# WIFI_BT.net
KiCad netlist of a schematic drawn in Altium Designer
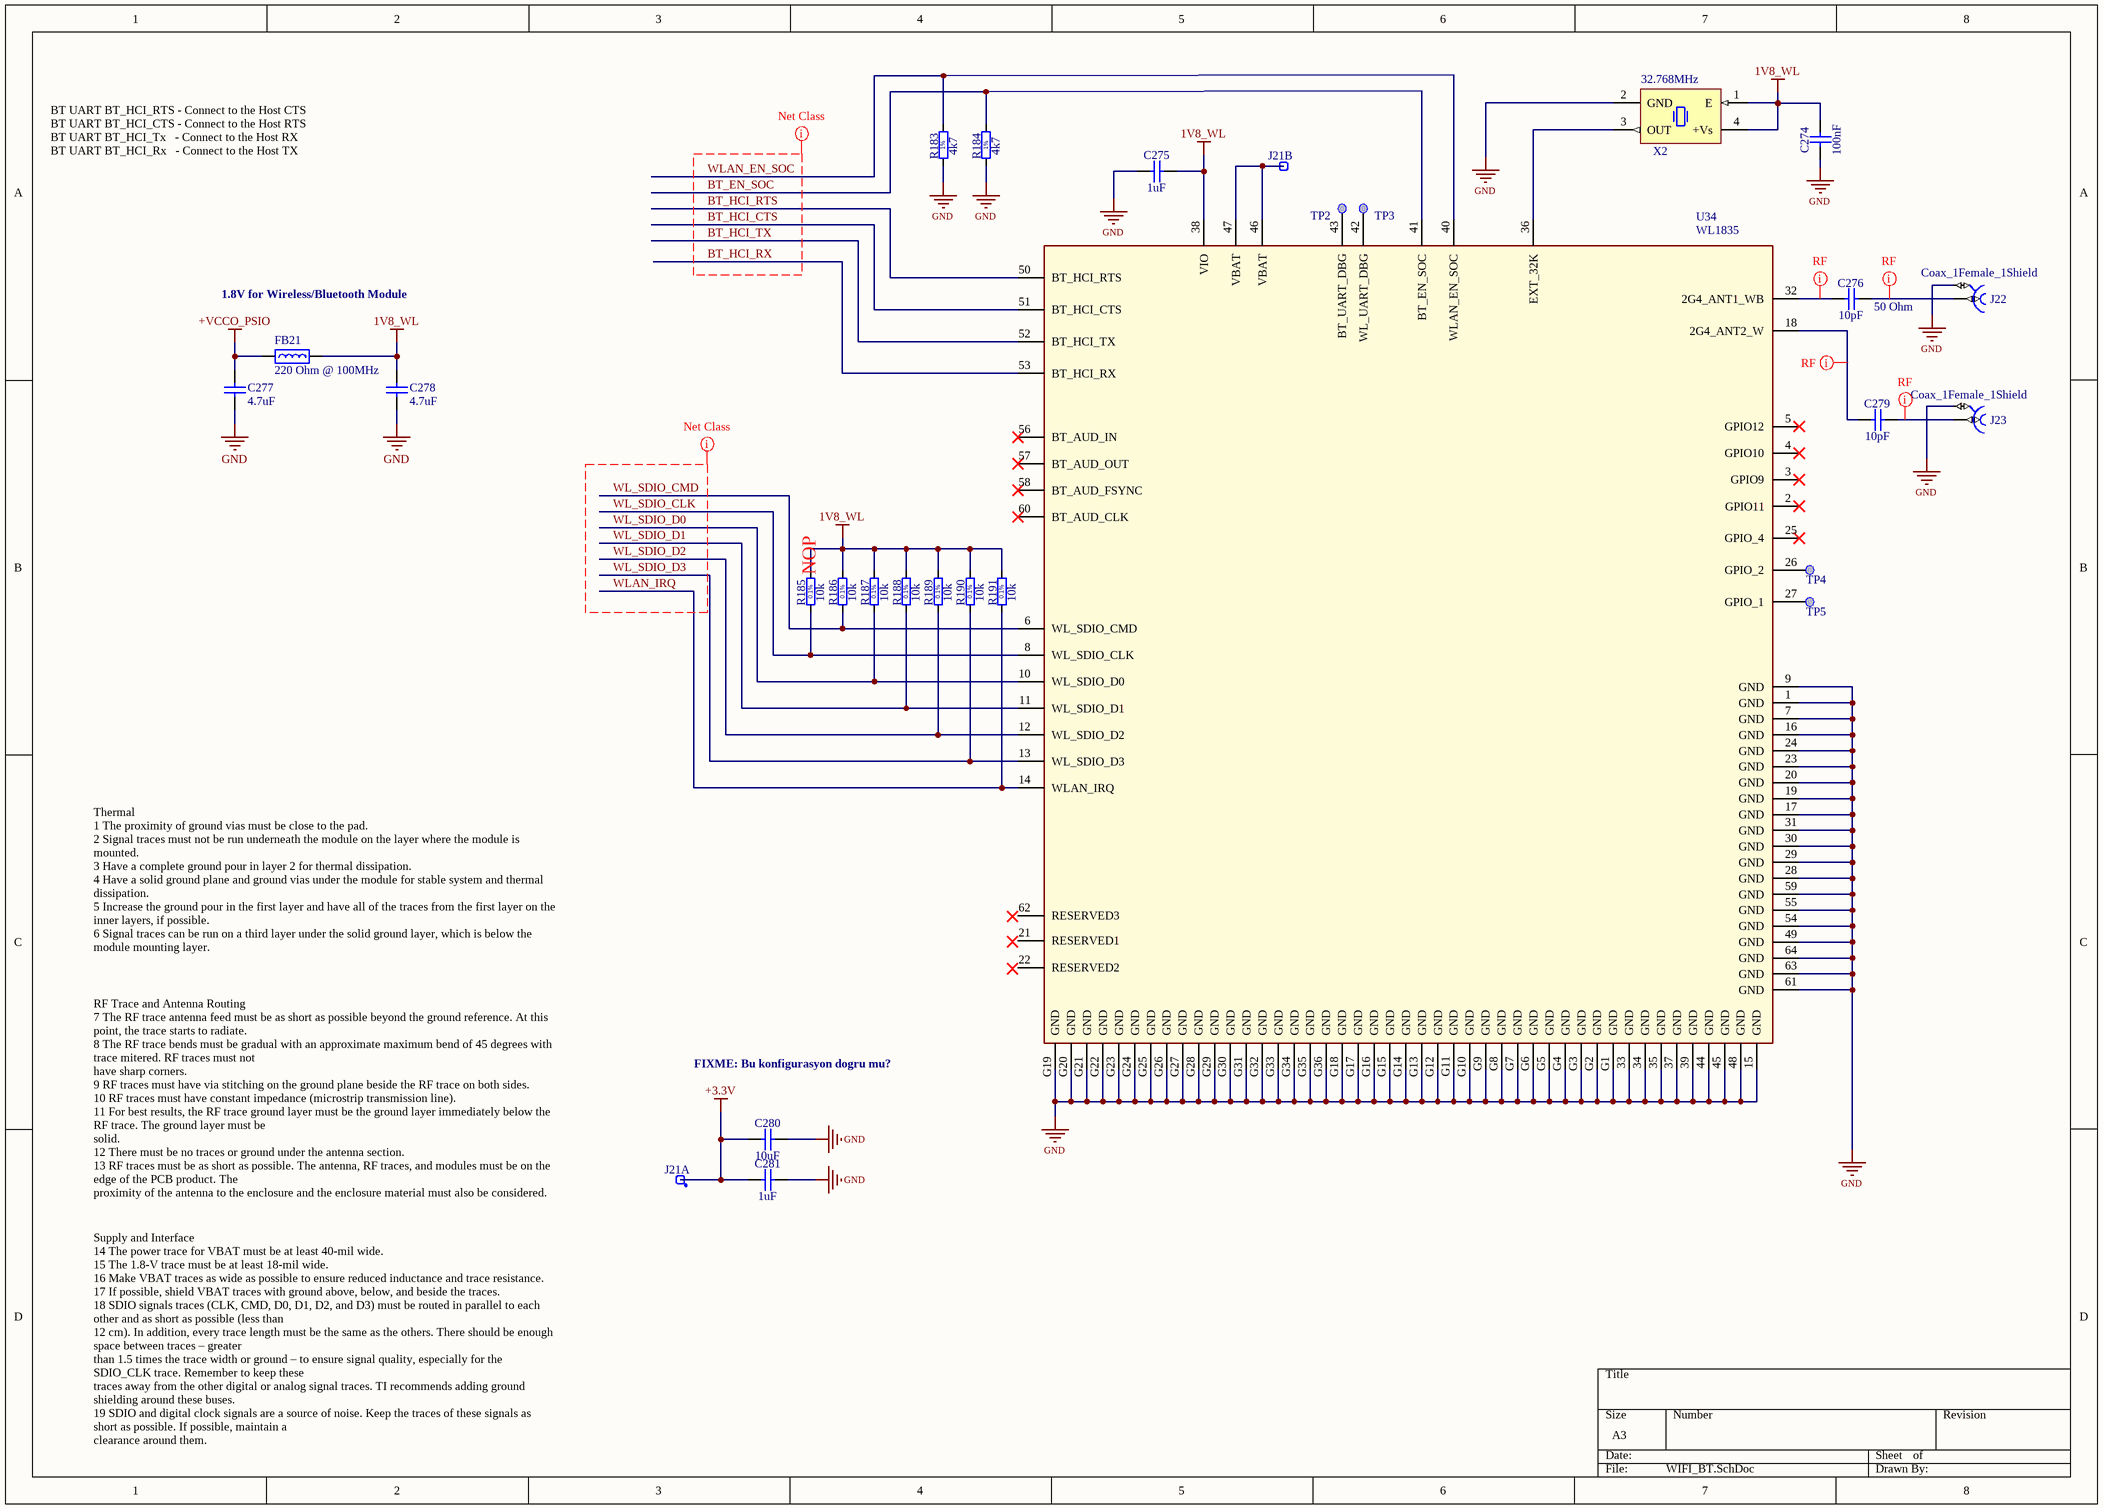
[diagram p0: WIFI_BT.SchDoc]

(export (version "E")
  (design (tool "Eeschema 10.0.6"))
  (components
    (comp (ref "C274")
      (value "100nF")
      (footprint "Ultrascale_PcbLib:CAPC1608X87N")
      (description "Non-polarised capacitor")
      (fields
        (field (name "PART NUMBER") "CC0603_100NF_50V_10%_X7R")
        (field (name "VOLTAGE") "50V")
        (field (name "AUTHOR") "CERN DEM JLC")
      )
      (libsource (lib "") (part "Capacitor - non polarized_1"))
    )
    (comp (ref "C275")
      (value "1uF")
      (footprint "Ultrascale_PcbLib:CAPC1608X87N")
      (description "Non-polarised capacitor")
      (fields
        (field (name "PART NUMBER") "CC0603_1UF_25V_10%_X7R")
        (field (name "VOLTAGE") "25V")
        (field (name "AUTHOR") "CERN DEM JLC")
      )
      (libsource (lib "Ultrascale_SchLib") (part "Capacitor - non polarized"))
    )
    (comp (ref "C276")
      (value "10pF")
      (footprint "Ultrascale_PcbLib:CAPC1608X87N")
      (description "Non-polarised capacitor")
      (fields
        (field (name "PART NUMBER") "CC0603_10PF_50V_5%_NP0")
        (field (name "VOLTAGE") "50V")
        (field (name "AUTHOR") "CERN DEM JLC")
      )
      (libsource (lib "Ultrascale_SchLib") (part "Capacitor - non polarized"))
    )
    (comp (ref "C277")
      (value "4.7uF")
      (footprint "CAPC1005L_0402")
      (description "CAP CER 4.7UF 10V X5R 0402")
      (fields (field (name "VOLTAGE") "10V") (field (name "TOLERANCE") "10%"))
      (libsource (lib "Ultrascale_SchLib") (part "CAPCER0402X5R4U710V_10T"))
    )
    (comp (ref "C278")
      (value "4.7uF")
      (footprint "CAPC1005L_0402")
      (description "CAP CER 4.7UF 10V X5R 0402")
      (fields (field (name "VOLTAGE") "10V") (field (name "TOLERANCE") "10%"))
      (libsource (lib "Ultrascale_SchLib") (part "CAPCER0402X5R4U710V_10T"))
    )
    (comp (ref "C279")
      (value "10pF")
      (footprint "Ultrascale_PcbLib:CAPC1608X87N")
      (description "Non-polarised capacitor")
      (fields
        (field (name "PART NUMBER") "CC0603_10PF_50V_5%_NP0")
        (field (name "VOLTAGE") "50V")
        (field (name "AUTHOR") "CERN DEM JLC")
      )
      (libsource (lib "Ultrascale_SchLib") (part "Capacitor - non polarized"))
    )
    (comp (ref "C280")
      (value "10uF")
      (footprint "Ultrascale_PcbLib:CAPC2012X135N")
      (description "Non-polarised capacitor")
      (fields
        (field (name "PART NUMBER") "CC0805_10UF_10V_10%_X7R")
        (field (name "VOLTAGE") "10V")
        (field (name "AUTHOR") "CERN DEM JLC")
      )
      (libsource (lib "Ultrascale_SchLib") (part "Capacitor - non polarized"))
    )
    (comp (ref "C281")
      (value "1uF")
      (footprint "Ultrascale_PcbLib:CAPC1608X87N")
      (description "Non-polarised capacitor")
      (fields
        (field (name "PART NUMBER") "CC0603_1UF_25V_10%_X7R")
        (field (name "VOLTAGE") "25V")
        (field (name "AUTHOR") "CERN DEM JLC")
      )
      (libsource (lib "Ultrascale_SchLib") (part "Capacitor - non polarized"))
    )
    (comp (ref "FB21")
      (value "BEAD0603_220_2A5_40M")
      (footprint "INDC1608N_0603")
      (description "FERRITE BEAD 220 OHM 0603 1LN")
      (fields (field (name "IMPEDANCE @ FREQUENCY") "220 Ohm @ 100MHz"))
      (libsource (lib "Ultrascale_SchLib") (part "BEAD0603_220_2A5_40M"))
    )
    (comp (ref "J21")
      (value "Test Point")
      (footprint "Ultrascale_PcbLib:COMATEL_385.0358.1.02.400")
      (description "2 Mini Wire-Wrap Contact Strip Header")
      (fields
        (field (name "PART NUMBER") "COMATEL_385.0358.1.02.400")
        (field (name "MANUFACTURER") "KONTEK COMATEL")
        (field (name "AUTHOR") "CERN DEM JLC")
      )
      (libsource (lib "Ultrascale_SchLib") (part "Wire-Wrap Contact x2"))
    )
    (comp (ref "J22")
      (value "Coax_1Female_1Shield")
      (footprint "Ultrascale_PcbLib:HUBER-SUHNER_82 SMA-50-0-41/133 NE")
      (fields
        (field (name "PART NUMBER") "HUBER-SUHNER_82_SMA-50-0-41/133_NE")
        (field (name "MANUFACTURER") "AMPHENOL CONNEX")
        (field (name "MANUFACTURER PART NUMBER") "132134")
        (field (name "AUTHOR") "CERN DEM JLC")
      )
      (libsource (lib "Ultrascale_SchLib") (part "Coax_1Female_1Shield"))
    )
    (comp (ref "J23")
      (value "Coax_1Female_1Shield")
      (footprint "Ultrascale_PcbLib:HUBER-SUHNER_82 SMA-50-0-41/133 NE")
      (fields
        (field (name "PART NUMBER") "HUBER-SUHNER_82_SMA-50-0-41/133_NE")
        (field (name "MANUFACTURER") "AMPHENOL CONNEX")
        (field (name "MANUFACTURER PART NUMBER") "132134")
        (field (name "AUTHOR") "CERN DEM JLC")
      )
      (libsource (lib "Ultrascale_SchLib") (part "Coax_1Female_1Shield"))
    )
    (comp (ref "R183")
      (value "4k7")
      (footprint "Ultrascale_PcbLib:RESC1608X55N")
      (description "Resistor - 1%")
      (fields
        (field (name "PART NUMBER") "R0603_4K7_1%_0.1W_100PPM")
        (field (name "POWER") "0.1W")
        (field (name "AUTHOR") "CERN DEM JLC")
      )
      (libsource (lib "Ultrascale_SchLib") (part "Resistor - 1%"))
    )
    (comp (ref "R184")
      (value "4k7")
      (footprint "Ultrascale_PcbLib:RESC1608X55N")
      (description "Resistor - 1%")
      (fields
        (field (name "PART NUMBER") "R0603_4K7_1%_0.1W_100PPM")
        (field (name "POWER") "0.1W")
        (field (name "AUTHOR") "CERN DEM JLC")
      )
      (libsource (lib "Ultrascale_SchLib") (part "Resistor - 1%"))
    )
    (comp (ref "R185")
      (value "10k")
      (footprint "Ultrascale_PcbLib:RESC1608X55N")
      (description "Resistor - 0.1%")
      (fields
        (field (name "PART NUMBER") "R0603_10K_0.1%_0.063W_10PPM")
        (field (name "POWER") "0.063W")
        (field (name "AUTHOR") "CERN DEM JLC")
      )
      (libsource (lib "Ultrascale_SchLib") (part "Resistor - 0.1%"))
    )
    (comp (ref "R186")
      (value "10k")
      (footprint "Ultrascale_PcbLib:RESC1608X55N")
      (description "Resistor - 0.1%")
      (fields
        (field (name "PART NUMBER") "R0603_10K_0.1%_0.063W_10PPM")
        (field (name "POWER") "0.063W")
        (field (name "AUTHOR") "CERN DEM JLC")
      )
      (libsource (lib "Ultrascale_SchLib") (part "Resistor - 0.1%"))
    )
    (comp (ref "R187")
      (value "10k")
      (footprint "Ultrascale_PcbLib:RESC1608X55N")
      (description "Resistor - 0.1%")
      (fields
        (field (name "PART NUMBER") "R0603_10K_0.1%_0.063W_10PPM")
        (field (name "POWER") "0.063W")
        (field (name "AUTHOR") "CERN DEM JLC")
      )
      (libsource (lib "Ultrascale_SchLib") (part "Resistor - 0.1%"))
    )
    (comp (ref "R188")
      (value "10k")
      (footprint "Ultrascale_PcbLib:RESC1608X55N")
      (description "Resistor - 0.1%")
      (fields
        (field (name "PART NUMBER") "R0603_10K_0.1%_0.063W_10PPM")
        (field (name "POWER") "0.063W")
        (field (name "AUTHOR") "CERN DEM JLC")
      )
      (libsource (lib "Ultrascale_SchLib") (part "Resistor - 0.1%"))
    )
    (comp (ref "R189")
      (value "10k")
      (footprint "Ultrascale_PcbLib:RESC1608X55N")
      (description "Resistor - 0.1%")
      (fields
        (field (name "PART NUMBER") "R0603_10K_0.1%_0.063W_10PPM")
        (field (name "POWER") "0.063W")
        (field (name "AUTHOR") "CERN DEM JLC")
      )
      (libsource (lib "Ultrascale_SchLib") (part "Resistor - 0.1%"))
    )
    (comp (ref "R190")
      (value "10k")
      (footprint "Ultrascale_PcbLib:RESC1608X55N")
      (description "Resistor - 0.1%")
      (fields
        (field (name "PART NUMBER") "R0603_10K_0.1%_0.063W_10PPM")
        (field (name "POWER") "0.063W")
        (field (name "AUTHOR") "CERN DEM JLC")
      )
      (libsource (lib "Ultrascale_SchLib") (part "Resistor - 0.1%"))
    )
    (comp (ref "R191")
      (value "10k")
      (footprint "Ultrascale_PcbLib:RESC1608X55N")
      (description "Resistor - 0.1%")
      (fields
        (field (name "PART NUMBER") "R0603_10K_0.1%_0.063W_10PPM")
        (field (name "POWER") "0.063W")
        (field (name "AUTHOR") "CERN DEM JLC")
      )
      (libsource (lib "Ultrascale_SchLib") (part "Resistor - 0.1%"))
    )
    (comp (ref "TP2")
      (value "TP")
      (footprint "Ultrascale_PcbLib:TP")
      (description "Test Point")
      (libsource (lib "Ultrascale_SchLib") (part "Test Point"))
    )
    (comp (ref "TP3")
      (value "TP")
      (footprint "Ultrascale_PcbLib:TP")
      (description "Test Point")
      (libsource (lib "Ultrascale_SchLib") (part "Test Point"))
    )
    (comp (ref "TP4")
      (value "TP")
      (footprint "Ultrascale_PcbLib:TP")
      (description "Test Point")
      (libsource (lib "Ultrascale_SchLib") (part "Test Point"))
    )
    (comp (ref "TP5")
      (value "TP")
      (footprint "Ultrascale_PcbLib:TP")
      (description "Test Point")
      (libsource (lib "Ultrascale_SchLib") (part "Test Point"))
    )
    (comp (ref "U34")
      (value "WL1835")
      (footprint "Ultrascale_PcbLib:E-13.4X13.3-N100_0.75-TOP")
      (description "MODULE WIFI WILINK")
      (fields
        (field (name "MANUFACTURER PART NUMBER") "WL1835MODGBMOCR")
        (field (name "MANUFACTURER") "Texas Instruments")
      )
      (libsource (lib "Ultrascale_SchLib") (part "WL1835"))
    )
    (comp (ref "X2")
      (value "32.768MHz")
      (footprint "Ultrascale_PcbLib:OSCSC508P500X700X180-4N")
      (description "Oscillator 4 pins 1=E 2=GND 3=OUT 4=+Vs")
      (fields
        (field (name "PART NUMBER") "OSC_32.7688MHZ_RAKON_LF SPXO019203")
        (field (name "MANUFACTURER") "EPSON")
        (field (name "AUTHOR") "CERN DEM JLC")
      )
      (libsource (lib "Ultrascale_SchLib") (part "Oscillator 1E 2GND 3OUT 4Vs"))
    )
  )
  (nets
    (net (code "1") (name "+3.3V") (class "Default")
      (node (ref "C280") (pin "1") (pinfunction "1_1") (pintype "passive"))
      (node (ref "C281") (pin "1") (pinfunction "1_1") (pintype "passive"))
      (node (ref "J21") (pin "1") (pinfunction "1_1") (pintype "bidirectional"))
    )
    (net (code "2") (name "+VCCO_PSIO") (class "Default")
      (node (ref "C277") (pin "2") (pinfunction "2_2") (pintype "passive"))
      (node (ref "FB21") (pin "1") (pinfunction "1_1") (pintype "passive"))
    )
    (net (code "3") (name "/BT_EN_SOC") (class "Default")
      (node (ref "R184") (pin "2") (pinfunction "2_2") (pintype "passive"))
      (node (ref "U34") (pin "41") (pinfunction "BT_EN_SOC_41") (pintype "passive"))
    )
    (net (code "4") (name "/BT_HCI_CTS") (class "Default")
      (node (ref "U34") (pin "51") (pinfunction "BT_HCI_CTS_51") (pintype "passive"))
    )
    (net (code "5") (name "/BT_HCI_RTS") (class "Default")
      (node (ref "U34") (pin "50") (pinfunction "BT_HCI_RTS_50") (pintype "passive"))
    )
    (net (code "6") (name "/BT_HCI_RX") (class "Default")
      (node (ref "U34") (pin "53") (pinfunction "BT_HCI_RX_53") (pintype "passive"))
    )
    (net (code "7") (name "/BT_HCI_TX") (class "Default")
      (node (ref "U34") (pin "52") (pinfunction "BT_HCI_TX_52") (pintype "passive"))
    )
    (net (code "8") (name "/WLAN_EN_SOC") (class "Default")
      (node (ref "R183") (pin "2") (pinfunction "2_2") (pintype "passive"))
      (node (ref "U34") (pin "40") (pinfunction "WLAN_EN_SOC_40") (pintype "passive"))
    )
    (net (code "9") (name "/WLAN_IRQ") (class "Default")
      (node (ref "R191") (pin "1") (pinfunction "1_1") (pintype "passive"))
      (node (ref "U34") (pin "14") (pinfunction "WLAN_IRQ_14") (pintype "passive"))
    )
    (net (code "10") (name "/WL_SDIO_CLK") (class "Default")
      (node (ref "R185") (pin "1") (pinfunction "1_1") (pintype "passive"))
      (node (ref "U34") (pin "8") (pinfunction "WL_SDIO_CLK_8") (pintype "passive"))
    )
    (net (code "11") (name "/WL_SDIO_CMD") (class "Default")
      (node (ref "R186") (pin "1") (pinfunction "1_1") (pintype "passive"))
      (node (ref "U34") (pin "6") (pinfunction "WL_SDIO_CMD_6") (pintype "passive"))
    )
    (net (code "12") (name "/WL_SDIO_D0") (class "Default")
      (node (ref "R187") (pin "1") (pinfunction "1_1") (pintype "passive"))
      (node (ref "U34") (pin "10") (pinfunction "WL_SDIO_D0_10") (pintype "passive"))
    )
    (net (code "13") (name "/WL_SDIO_D1") (class "Default")
      (node (ref "R188") (pin "1") (pinfunction "1_1") (pintype "passive"))
      (node (ref "U34") (pin "11") (pinfunction "WL_SDIO_D1_11") (pintype "passive"))
    )
    (net (code "14") (name "/WL_SDIO_D2") (class "Default")
      (node (ref "R189") (pin "1") (pinfunction "1_1") (pintype "passive"))
      (node (ref "U34") (pin "12") (pinfunction "WL_SDIO_D2_12") (pintype "passive"))
    )
    (net (code "15") (name "/WL_SDIO_D3") (class "Default")
      (node (ref "R190") (pin "1") (pinfunction "1_1") (pintype "passive"))
      (node (ref "U34") (pin "13") (pinfunction "WL_SDIO_D3_13") (pintype "passive"))
    )
    (net (code "16") (name "1V8_WL") (class "Default")
      (node (ref "C274") (pin "2") (pinfunction "2_2") (pintype "passive"))
      (node (ref "C275") (pin "2") (pinfunction "2_2") (pintype "passive"))
      (node (ref "C278") (pin "2") (pinfunction "2_2") (pintype "passive"))
      (node (ref "FB21") (pin "2") (pinfunction "2_2") (pintype "passive"))
      (node (ref "R185") (pin "2") (pinfunction "2_2") (pintype "passive"))
      (node (ref "R186") (pin "2") (pinfunction "2_2") (pintype "passive"))
      (node (ref "R187") (pin "2") (pinfunction "2_2") (pintype "passive"))
      (node (ref "R188") (pin "2") (pinfunction "2_2") (pintype "passive"))
      (node (ref "R189") (pin "2") (pinfunction "2_2") (pintype "passive"))
      (node (ref "R190") (pin "2") (pinfunction "2_2") (pintype "passive"))
      (node (ref "R191") (pin "2") (pinfunction "2_2") (pintype "passive"))
      (node (ref "U34") (pin "38") (pinfunction "VIO_38") (pintype "power_in"))
      (node (ref "X2") (pin "1") (pinfunction "E_1") (pintype "input"))
      (node (ref "X2") (pin "4") (pinfunction "+Vs_4") (pintype "power_in"))
    )
    (net (code "17") (name "GND") (class "Default")
      (node (ref "C274") (pin "1") (pinfunction "1_1") (pintype "passive"))
      (node (ref "C275") (pin "1") (pinfunction "1_1") (pintype "passive"))
      (node (ref "C277") (pin "1") (pinfunction "1_1") (pintype "passive"))
      (node (ref "C278") (pin "1") (pinfunction "1_1") (pintype "passive"))
      (node (ref "C280") (pin "2") (pinfunction "2_2") (pintype "passive"))
      (node (ref "C281") (pin "2") (pinfunction "2_2") (pintype "passive"))
      (node (ref "J22") (pin "2") (pinfunction "2_2") (pintype "bidirectional"))
      (node (ref "J23") (pin "2") (pinfunction "2_2") (pintype "bidirectional"))
      (node (ref "R183") (pin "1") (pinfunction "1_1") (pintype "passive"))
      (node (ref "R184") (pin "1") (pinfunction "1_1") (pintype "passive"))
      (node (ref "U34") (pin "1") (pinfunction "GND_1") (pintype "power_in"))
      (node (ref "U34") (pin "15") (pinfunction "GND_15") (pintype "power_in"))
      (node (ref "U34") (pin "16") (pinfunction "GND_16") (pintype "power_in"))
      (node (ref "U34") (pin "17") (pinfunction "GND_17") (pintype "power_in"))
      (node (ref "U34") (pin "19") (pinfunction "GND_19") (pintype "power_in"))
      (node (ref "U34") (pin "20") (pinfunction "GND_20") (pintype "power_in"))
      (node (ref "U34") (pin "23") (pinfunction "GND_23") (pintype "power_in"))
      (node (ref "U34") (pin "24") (pinfunction "GND_24") (pintype "power_in"))
      (node (ref "U34") (pin "28") (pinfunction "GND_28") (pintype "power_in"))
      (node (ref "U34") (pin "29") (pinfunction "GND_29") (pintype "power_in"))
      (node (ref "U34") (pin "30") (pinfunction "GND_30") (pintype "power_in"))
      (node (ref "U34") (pin "31") (pinfunction "GND_31") (pintype "power_in"))
      (node (ref "U34") (pin "33") (pinfunction "GND_33") (pintype "power_in"))
      (node (ref "U34") (pin "34") (pinfunction "GND_34") (pintype "power_in"))
      (node (ref "U34") (pin "35") (pinfunction "GND_35") (pintype "power_in"))
      (node (ref "U34") (pin "37") (pinfunction "GND_37") (pintype "power_in"))
      (node (ref "U34") (pin "39") (pinfunction "GND_39") (pintype "power_in"))
      (node (ref "U34") (pin "44") (pinfunction "GND_44") (pintype "power_in"))
      (node (ref "U34") (pin "45") (pinfunction "GND_45") (pintype "power_in"))
      (node (ref "U34") (pin "48") (pinfunction "GND_48") (pintype "power_in"))
      (node (ref "U34") (pin "49") (pinfunction "GND_49") (pintype "power_in"))
      (node (ref "U34") (pin "54") (pinfunction "GND_54") (pintype "power_in"))
      (node (ref "U34") (pin "55") (pinfunction "GND_55") (pintype "power_in"))
      (node (ref "U34") (pin "59") (pinfunction "GND_59") (pintype "power_in"))
      (node (ref "U34") (pin "61") (pinfunction "GND_61") (pintype "power_in"))
      (node (ref "U34") (pin "63") (pinfunction "GND_63") (pintype "power_in"))
      (node (ref "U34") (pin "64") (pinfunction "GND_64") (pintype "power_in"))
      (node (ref "U34") (pin "7") (pinfunction "GND_7") (pintype "power_in"))
      (node (ref "U34") (pin "9") (pinfunction "GND_9") (pintype "power_in"))
      (node (ref "U34") (pin "G1") (pinfunction "GND_G1") (pintype "power_in"))
      (node (ref "U34") (pin "G10") (pinfunction "GND_G10") (pintype "power_in"))
      (node (ref "U34") (pin "G11") (pinfunction "GND_G11") (pintype "power_in"))
      (node (ref "U34") (pin "G12") (pinfunction "GND_G12") (pintype "power_in"))
      (node (ref "U34") (pin "G13") (pinfunction "GND_G13") (pintype "power_in"))
      (node (ref "U34") (pin "G14") (pinfunction "GND_G14") (pintype "power_in"))
      (node (ref "U34") (pin "G15") (pinfunction "GND_G15") (pintype "power_in"))
      (node (ref "U34") (pin "G16") (pinfunction "GND_G16") (pintype "power_in"))
      (node (ref "U34") (pin "G17") (pinfunction "GND_G17") (pintype "power_in"))
      (node (ref "U34") (pin "G18") (pinfunction "GND_G18") (pintype "power_in"))
      (node (ref "U34") (pin "G19") (pinfunction "GND_G19") (pintype "power_in"))
      (node (ref "U34") (pin "G2") (pinfunction "GND_G2") (pintype "power_in"))
      (node (ref "U34") (pin "G20") (pinfunction "GND_G20") (pintype "power_in"))
      (node (ref "U34") (pin "G21") (pinfunction "GND_G21") (pintype "power_in"))
      (node (ref "U34") (pin "G22") (pinfunction "GND_G22") (pintype "power_in"))
      (node (ref "U34") (pin "G23") (pinfunction "GND_G23") (pintype "power_in"))
      (node (ref "U34") (pin "G24") (pinfunction "GND_G24") (pintype "power_in"))
      (node (ref "U34") (pin "G25") (pinfunction "GND_G25") (pintype "power_in"))
      (node (ref "U34") (pin "G26") (pinfunction "GND_G26") (pintype "power_in"))
      (node (ref "U34") (pin "G27") (pinfunction "GND_G27") (pintype "power_in"))
      (node (ref "U34") (pin "G28") (pinfunction "GND_G28") (pintype "power_in"))
      (node (ref "U34") (pin "G29") (pinfunction "GND_G29") (pintype "power_in"))
      (node (ref "U34") (pin "G3") (pinfunction "GND_G3") (pintype "power_in"))
      (node (ref "U34") (pin "G30") (pinfunction "GND_G30") (pintype "power_in"))
      (node (ref "U34") (pin "G31") (pinfunction "GND_G31") (pintype "power_in"))
      (node (ref "U34") (pin "G32") (pinfunction "GND_G32") (pintype "power_in"))
      (node (ref "U34") (pin "G33") (pinfunction "GND_G33") (pintype "power_in"))
      (node (ref "U34") (pin "G34") (pinfunction "GND_G34") (pintype "power_in"))
      (node (ref "U34") (pin "G35") (pinfunction "GND_G35") (pintype "power_in"))
      (node (ref "U34") (pin "G36") (pinfunction "GND_G36") (pintype "power_in"))
      (node (ref "U34") (pin "G4") (pinfunction "GND_G4") (pintype "power_in"))
      (node (ref "U34") (pin "G5") (pinfunction "GND_G5") (pintype "power_in"))
      (node (ref "U34") (pin "G6") (pinfunction "GND_G6") (pintype "power_in"))
      (node (ref "U34") (pin "G7") (pinfunction "GND_G7") (pintype "power_in"))
      (node (ref "U34") (pin "G8") (pinfunction "GND_G8") (pintype "power_in"))
      (node (ref "U34") (pin "G9") (pinfunction "GND_G9") (pintype "power_in"))
      (node (ref "X2") (pin "2") (pinfunction "GND_2") (pintype "power_in"))
    )
    (net (code "18") (name "Net-(C276-Pad2)") (class "Default")
      (node (ref "C276") (pin "2") (pinfunction "2_2") (pintype "passive"))
      (node (ref "J22") (pin "1") (pinfunction "1_1") (pintype "bidirectional"))
    )
    (net (code "19") (name "Net-(C279-Pad2)") (class "Default")
      (node (ref "C279") (pin "2") (pinfunction "2_2") (pintype "passive"))
      (node (ref "J23") (pin "1") (pinfunction "1_1") (pintype "bidirectional"))
    )
    (net (code "20") (name "Net-(J21-Pad2)") (class "Default")
      (node (ref "J21") (pin "2") (pinfunction "2_2") (pintype "bidirectional"))
      (node (ref "U34") (pin "46") (pinfunction "VBAT_46") (pintype "power_in"))
      (node (ref "U34") (pin "47") (pinfunction "VBAT_47") (pintype "power_in"))
    )
    (net (code "21") (name "Net-(U34-2G4_ANT1_WB)") (class "Default")
      (node (ref "C276") (pin "1") (pinfunction "1_1") (pintype "passive"))
      (node (ref "U34") (pin "32") (pinfunction "2G4_ANT1_WB_32") (pintype "passive"))
    )
    (net (code "22") (name "Net-(U34-2G4_ANT2_W)") (class "Default")
      (node (ref "C279") (pin "1") (pinfunction "1_1") (pintype "passive"))
      (node (ref "U34") (pin "18") (pinfunction "2G4_ANT2_W_18") (pintype "passive"))
    )
    (net (code "23") (name "Net-(U34-BT_UART_DBG)") (class "Default")
      (node (ref "TP2") (pin "1") (pinfunction "1_1") (pintype "passive"))
      (node (ref "U34") (pin "43") (pinfunction "BT_UART_DBG_43") (pintype "passive"))
    )
    (net (code "24") (name "Net-(U34-EXT_32K)") (class "Default")
      (node (ref "U34") (pin "36") (pinfunction "EXT_32K_36") (pintype "passive"))
      (node (ref "X2") (pin "3") (pinfunction "OUT_3") (pintype "output"))
    )
    (net (code "25") (name "Net-(U34-GPIO_1)") (class "Default")
      (node (ref "TP5") (pin "1") (pinfunction "1_1") (pintype "passive"))
      (node (ref "U34") (pin "27") (pinfunction "GPIO_1_27") (pintype "passive"))
    )
    (net (code "26") (name "Net-(U34-GPIO_2)") (class "Default")
      (node (ref "TP4") (pin "1") (pinfunction "1_1") (pintype "passive"))
      (node (ref "U34") (pin "26") (pinfunction "GPIO_2_26") (pintype "passive"))
    )
    (net (code "27") (name "Net-(U34-WL_UART_DBG)") (class "Default")
      (node (ref "TP3") (pin "1") (pinfunction "1_1") (pintype "passive"))
      (node (ref "U34") (pin "42") (pinfunction "WL_UART_DBG_42") (pintype "passive"))
    )
    (net (code "28") (name "unconnected-(U34-BT_AUD_CLK-Pad60)") (class "Default")
      (node (ref "U34") (pin "60") (pinfunction "BT_AUD_CLK_60") (pintype "passive+no_connect"))
    )
    (net (code "29") (name "unconnected-(U34-BT_AUD_FSYNC-Pad58)") (class "Default")
      (node (ref "U34") (pin "58") (pinfunction "BT_AUD_FSYNC_58") (pintype "passive+no_connect"))
    )
    (net (code "30") (name "unconnected-(U34-BT_AUD_IN-Pad56)") (class "Default")
      (node (ref "U34") (pin "56") (pinfunction "BT_AUD_IN_56") (pintype "passive+no_connect"))
    )
    (net (code "31") (name "unconnected-(U34-BT_AUD_OUT-Pad57)") (class "Default")
      (node (ref "U34") (pin "57") (pinfunction "BT_AUD_OUT_57") (pintype "passive+no_connect"))
    )
    (net (code "32") (name "unconnected-(U34-GPIO9-Pad3)") (class "Default")
      (node (ref "U34") (pin "3") (pinfunction "GPIO9_3") (pintype "passive+no_connect"))
    )
    (net (code "33") (name "unconnected-(U34-GPIO10-Pad4)") (class "Default")
      (node (ref "U34") (pin "4") (pinfunction "GPIO10_4") (pintype "passive+no_connect"))
    )
    (net (code "34") (name "unconnected-(U34-GPIO11-Pad2)") (class "Default")
      (node (ref "U34") (pin "2") (pinfunction "GPIO11_2") (pintype "passive+no_connect"))
    )
    (net (code "35") (name "unconnected-(U34-GPIO12-Pad5)") (class "Default")
      (node (ref "U34") (pin "5") (pinfunction "GPIO12_5") (pintype "passive+no_connect"))
    )
    (net (code "36") (name "unconnected-(U34-GPIO_4-Pad25)") (class "Default")
      (node (ref "U34") (pin "25") (pinfunction "GPIO_4_25") (pintype "passive+no_connect"))
    )
    (net (code "37") (name "unconnected-(U34-RESERVED1-Pad21)") (class "Default")
      (node (ref "U34") (pin "21") (pinfunction "RESERVED1_21") (pintype "passive"))
    )
    (net (code "38") (name "unconnected-(U34-RESERVED2-Pad22)") (class "Default")
      (node (ref "U34") (pin "22") (pinfunction "RESERVED2_22") (pintype "passive"))
    )
    (net (code "39") (name "unconnected-(U34-RESERVED3-Pad62)") (class "Default")
      (node (ref "U34") (pin "62") (pinfunction "RESERVED3_62") (pintype "passive"))
    )
  )
)
